# Logic_IO_Unit_V2.net
KiCad netlist of a schematic drawn in Altium Designer
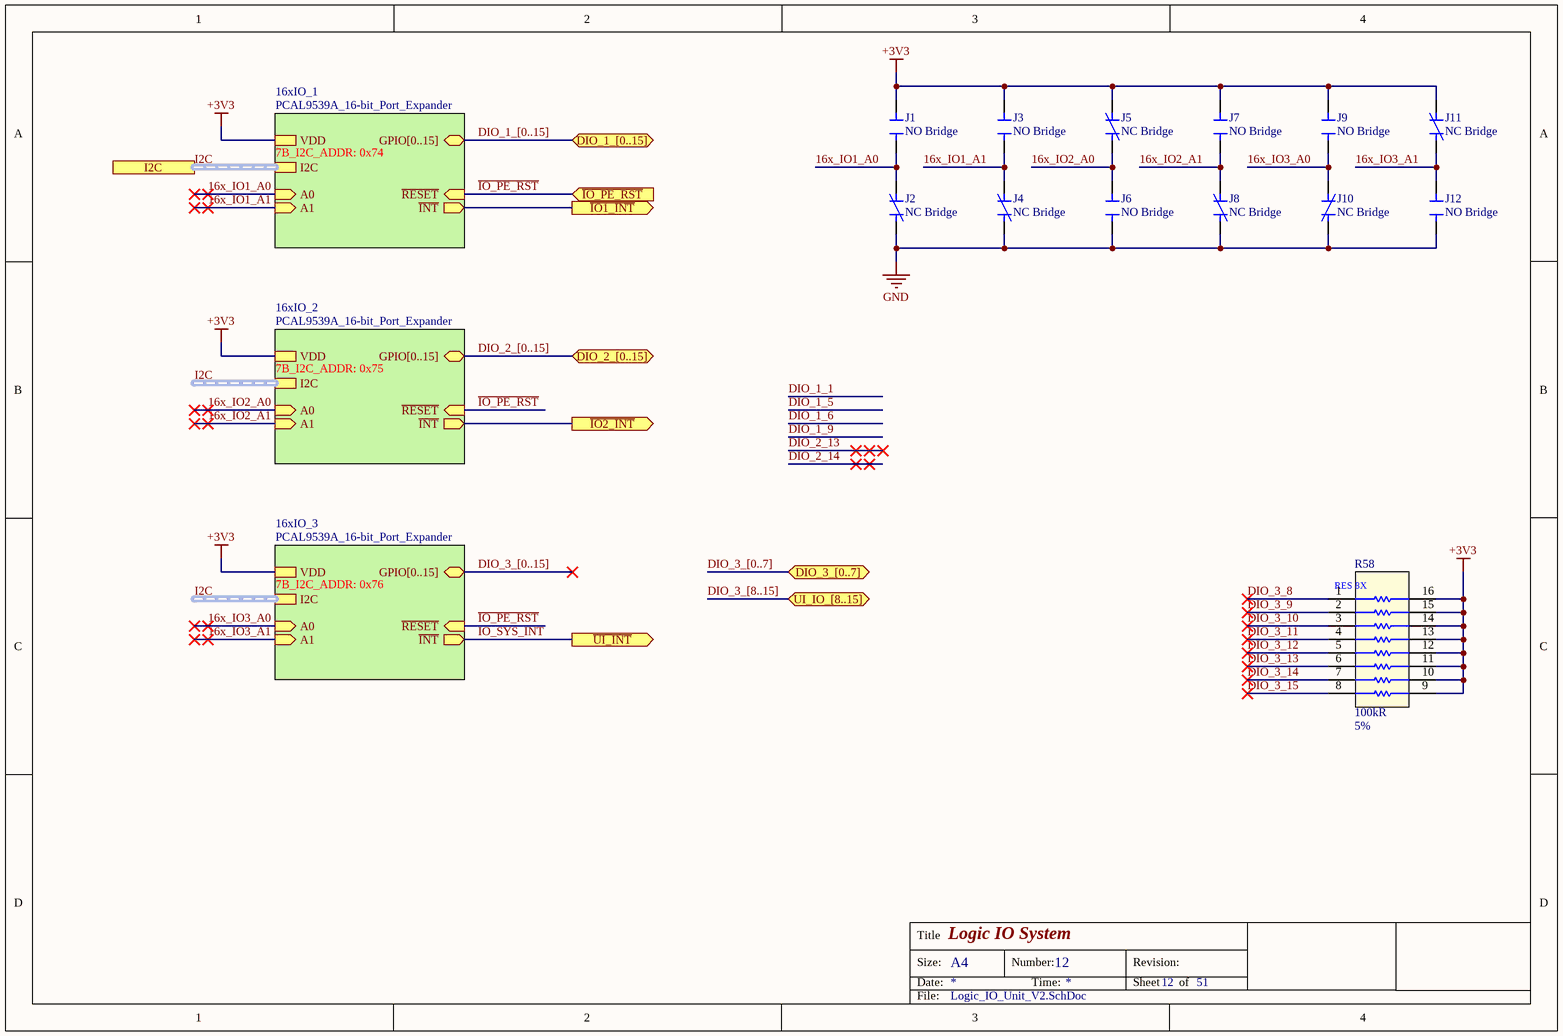
[diagram p0: Logic_IO_Unit_V2.SchDoc]

(export (version "E")
  (design (tool "Eeschema 10.0.6"))
  (components
    (comp (ref "J1")
      (value "NO Bridge")
      (footprint "NO_SolderBridge_0603")
      (description "NO PCB Bridge (May be closed by a solder blob)")
      (libsource (lib "BLDC_Motor_Driver") (part "NO Bridge"))
    )
    (comp (ref "J2")
      (value "NC Bridge")
      (footprint "NC_SolderBridge_0603")
      (description "NC PCB Bridge (May be opened by cutting the copper trace)")
      (libsource (lib "BLDC_Motor_Driver") (part "NC Bridge"))
    )
    (comp (ref "J3")
      (value "NO Bridge")
      (footprint "NO_SolderBridge_0603")
      (description "NO PCB Bridge (May be closed by a solder blob)")
      (libsource (lib "BLDC_Motor_Driver") (part "NO Bridge"))
    )
    (comp (ref "J4")
      (value "NC Bridge")
      (footprint "NC_SolderBridge_0603")
      (description "NC PCB Bridge (May be opened by cutting the copper trace)")
      (libsource (lib "BLDC_Motor_Driver") (part "NC Bridge"))
    )
    (comp (ref "J5")
      (value "NC Bridge")
      (footprint "NC_SolderBridge_0603")
      (description "NC PCB Bridge (May be opened by cutting the copper trace)")
      (libsource (lib "BLDC_Motor_Driver") (part "NC Bridge"))
    )
    (comp (ref "J6")
      (value "NO Bridge")
      (footprint "NO_SolderBridge_0603")
      (description "NO PCB Bridge (May be closed by a solder blob)")
      (libsource (lib "BLDC_Motor_Driver") (part "NO Bridge"))
    )
    (comp (ref "J7")
      (value "NO Bridge")
      (footprint "NO_SolderBridge_0603")
      (description "NO PCB Bridge (May be closed by a solder blob)")
      (libsource (lib "BLDC_Motor_Driver") (part "NO Bridge"))
    )
    (comp (ref "J8")
      (value "NC Bridge")
      (footprint "NC_SolderBridge_0603")
      (description "NC PCB Bridge (May be opened by cutting the copper trace)")
      (libsource (lib "BLDC_Motor_Driver") (part "NC Bridge"))
    )
    (comp (ref "J9")
      (value "NO Bridge")
      (footprint "NO_SolderBridge_0603")
      (description "NO PCB Bridge (May be closed by a solder blob)")
      (libsource (lib "BLDC_Motor_Driver") (part "NO Bridge"))
    )
    (comp (ref "J10")
      (value "NC Bridge")
      (footprint "NC_SolderBridge_0603")
      (description "NC PCB Bridge (May be opened by cutting the copper trace)")
      (libsource (lib "BLDC_Motor_Driver") (part "NC Bridge"))
    )
    (comp (ref "J11")
      (value "NC Bridge")
      (footprint "NC_SolderBridge_0603")
      (description "NC PCB Bridge (May be opened by cutting the copper trace)")
      (libsource (lib "BLDC_Motor_Driver") (part "NC Bridge"))
    )
    (comp (ref "J12")
      (value "NO Bridge")
      (footprint "NO_SolderBridge_0603")
      (description "NO PCB Bridge (May be closed by a solder blob)")
      (libsource (lib "BLDC_Motor_Driver") (part "NO Bridge"))
    )
    (comp (ref "R58")
      (value "RES ARRAY 8 RES 100K OHM 1606")
      (footprint "YAG_YC248")
      (fields
        (field (name "MANUFACTURER") "Yageo")
        (field (name "MANUFACTURER PART NUMBER") "YC248-JR-07100KL")
        (field (name "RESISTANCE") "100kR")
        (field (name "TOLERANCE") "5%")
      )
      (libsource (lib "resistors_smd") (part "RES ARRAY 8 RES 100K OHM 1606"))
    )
  )
  (nets
    (net (code "36") (name "+3V3") (class "Default")
      (node (ref "J1") (pin "2") (pinfunction "2_2") (pintype "passive"))
      (node (ref "J11") (pin "2") (pinfunction "2_2") (pintype "passive"))
      (node (ref "J3") (pin "2") (pinfunction "2_2") (pintype "passive"))
      (node (ref "J5") (pin "2") (pinfunction "2_2") (pintype "passive"))
      (node (ref "J7") (pin "2") (pinfunction "2_2") (pintype "passive"))
      (node (ref "J9") (pin "2") (pinfunction "2_2") (pintype "passive"))
      (node (ref "R58") (pin "10") (pinfunction "110_10") (pintype "passive"))
      (node (ref "R58") (pin "11") (pinfunction "111_11") (pintype "passive"))
      (node (ref "R58") (pin "12") (pinfunction "112_12") (pintype "passive"))
      (node (ref "R58") (pin "13") (pinfunction "113_13") (pintype "passive"))
      (node (ref "R58") (pin "14") (pinfunction "114_14") (pintype "passive"))
      (node (ref "R58") (pin "15") (pinfunction "115_15") (pintype "passive"))
      (node (ref "R58") (pin "16") (pinfunction "116_16") (pintype "passive"))
      (node (ref "R58") (pin "9") (pinfunction "19_9") (pintype "passive"))
    )
    (net (code "37") (name "/16x_IO1_A0") (class "Default")
      (node (ref "J1") (pin "1") (pinfunction "1_1") (pintype "passive"))
      (node (ref "J2") (pin "2") (pinfunction "2_2") (pintype "passive"))
    )
    (net (code "38") (name "/16x_IO1_A1") (class "Default")
      (node (ref "J3") (pin "1") (pinfunction "1_1") (pintype "passive"))
      (node (ref "J4") (pin "2") (pinfunction "2_2") (pintype "passive"))
    )
    (net (code "39") (name "/16x_IO2_A0") (class "Default")
      (node (ref "J5") (pin "1") (pinfunction "1_1") (pintype "passive"))
      (node (ref "J6") (pin "2") (pinfunction "2_2") (pintype "passive"))
    )
    (net (code "40") (name "/16x_IO2_A1") (class "Default")
      (node (ref "J7") (pin "1") (pinfunction "1_1") (pintype "passive"))
      (node (ref "J8") (pin "2") (pinfunction "2_2") (pintype "passive"))
    )
    (net (code "41") (name "/16x_IO3_A0") (class "Default")
      (node (ref "J10") (pin "2") (pinfunction "2_2") (pintype "passive"))
      (node (ref "J9") (pin "1") (pinfunction "1_1") (pintype "passive"))
    )
    (net (code "42") (name "/16x_IO3_A1") (class "Default")
      (node (ref "J11") (pin "1") (pinfunction "1_1") (pintype "passive"))
      (node (ref "J12") (pin "2") (pinfunction "2_2") (pintype "passive"))
    )
    (net (code "57") (name "/DIO_3_8") (class "Default")
      (node (ref "R58") (pin "1") (pinfunction "11_1") (pintype "passive+no_connect"))
    )
    (net (code "58") (name "/DIO_3_9") (class "Default")
      (node (ref "R58") (pin "2") (pinfunction "12_2") (pintype "passive+no_connect"))
    )
    (net (code "59") (name "/DIO_3_10") (class "Default")
      (node (ref "R58") (pin "3") (pinfunction "13_3") (pintype "passive+no_connect"))
    )
    (net (code "60") (name "/DIO_3_11") (class "Default")
      (node (ref "R58") (pin "4") (pinfunction "14_4") (pintype "passive+no_connect"))
    )
    (net (code "61") (name "/DIO_3_12") (class "Default")
      (node (ref "R58") (pin "5") (pinfunction "15_5") (pintype "passive+no_connect"))
    )
    (net (code "62") (name "/DIO_3_13") (class "Default")
      (node (ref "R58") (pin "6") (pinfunction "16_6") (pintype "passive+no_connect"))
    )
    (net (code "63") (name "/DIO_3_14") (class "Default")
      (node (ref "R58") (pin "7") (pinfunction "17_7") (pintype "passive+no_connect"))
    )
    (net (code "64") (name "/DIO_3_15") (class "Default")
      (node (ref "R58") (pin "8") (pinfunction "18_8") (pintype "passive+no_connect"))
    )
    (net (code "73") (name "GND") (class "Default")
      (node (ref "J10") (pin "1") (pinfunction "1_1") (pintype "passive"))
      (node (ref "J12") (pin "1") (pinfunction "1_1") (pintype "passive"))
      (node (ref "J2") (pin "1") (pinfunction "1_1") (pintype "passive"))
      (node (ref "J4") (pin "1") (pinfunction "1_1") (pintype "passive"))
      (node (ref "J6") (pin "1") (pinfunction "1_1") (pintype "passive"))
      (node (ref "J8") (pin "1") (pinfunction "1_1") (pintype "passive"))
    )
  )
)
